# Microcontroller.net
KiCad netlist of a schematic drawn in Altium Designer
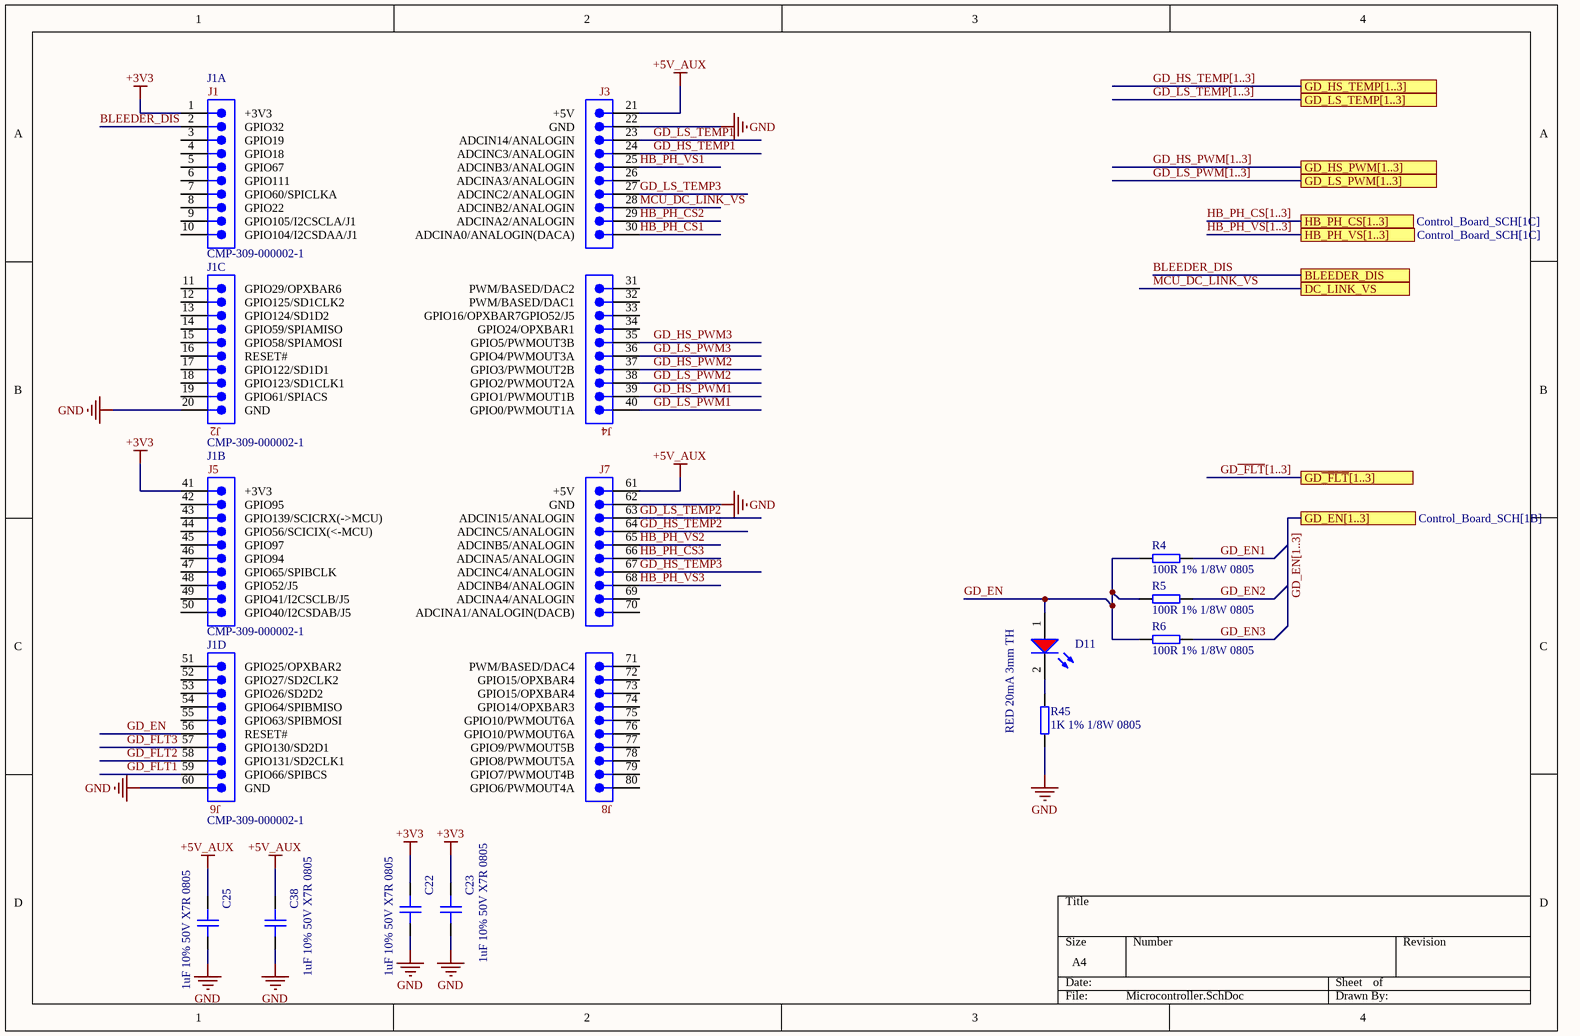
[diagram p0: Microcontroller.SchDoc]

(export (version "E")
  (design (tool "Eeschema 10.0.6"))
  (components
    (comp (ref "C22")
      (value "1uF 10% 50V X7R 0805")
      (footprint "CAPC2012X10N")
      (fields
        (field (name "MANUFACTURER PART NUMBER") "C2012X7R1H105K125AB")
        (field (name "MANUFACTURER") "TDK")
      )
      (libsource (lib "EMEA- E-Tech Racing- I'Escola d'Enginyeria de Barcelona Est") (part "68pF 10 630V C0G 0805"))
    )
    (comp (ref "C23")
      (value "1uF 10% 50V X7R 0805")
      (footprint "CAPC2012X10N")
      (fields
        (field (name "MANUFACTURER PART NUMBER") "C2012X7R1H105K125AB")
        (field (name "MANUFACTURER") "TDK")
      )
      (libsource (lib "EMEA- E-Tech Racing- I'Escola d'Enginyeria de Barcelona Est") (part "68pF 10 630V C0G 0805"))
    )
    (comp (ref "C25")
      (value "1uF 10% 50V X7R 0805")
      (footprint "CAPC2012X10N")
      (fields
        (field (name "MANUFACTURER PART NUMBER") "C2012X7R1H105K125AB")
        (field (name "MANUFACTURER") "TDK")
      )
      (libsource (lib "EMEA- E-Tech Racing- I'Escola d'Enginyeria de Barcelona Est") (part "68pF 10 630V C0G 0805"))
    )
    (comp (ref "C38")
      (value "1uF 10% 50V X7R 0805")
      (footprint "CAPC2012X10N")
      (fields
        (field (name "MANUFACTURER PART NUMBER") "C2012X7R1H105K125AB")
        (field (name "MANUFACTURER") "TDK")
      )
      (libsource (lib "EMEA- E-Tech Racing- I'Escola d'Enginyeria de Barcelona Est") (part "68pF 10 630V C0G 0805"))
    )
    (comp (ref "D11")
      (value "RED 20mA 3mm TH")
      (footprint "WL-TMRC_D3.95H5.3")
      (description "LED RED DIFFUSED 3MM ROUND T/H")
      (fields
        (field (name "MANUFACTURER") "Wurth Elektronik")
        (field (name "MANUFACTURER PART NUMBER") "151031SS06000")
      )
      (libsource (lib "EMEA- E-Tech Racing- I'Escola d'Enginyeria de Barcelona Est") (part "LED_Red_1A-2K"))
    )
    (comp (ref "J1")
      (value "CMP-309-000002-1")
      (footprint "LAUNCHXL-F28379D")
      (description "F28379D LaunchPad™ development kit for C2000™ Delfino™ MCU")
      (fields
        (field (name "MANUFACTURER") "Texas Instruments")
        (field (name "MANUFACTURER PART NUMBER") "LAUNCHXL-F28379D")
      )
      (libsource (lib "EMEA- E-Tech Racing- I'Escola d'Enginyeria de Barcelona Est") (part "CON80{colon} LAUNCHXL-F28379D"))
    )
    (comp (ref "R4")
      (value "100R 1% 1/8W 0805")
      (footprint "RESC2012X05N")
      (description "Res Thick Film 0805 100 Ohm 1% 0.125W ±100ppm/°C Molded SMD Paper T/R")
      (fields (field (name "TOLERANCE") "1%") (field (name "MANUFACTURER PART NUMBER") "RMCF0805FT100R"))
      (libsource (lib "EMEA- E-Tech Racing- I'Escola d'Enginyeria de Barcelona Est") (part "100R 1 1/8W 0805"))
    )
    (comp (ref "R5")
      (value "100R 1% 1/8W 0805")
      (footprint "RESC2012X05N")
      (description "Res Thick Film 0805 100 Ohm 1% 0.125W ±100ppm/°C Molded SMD Paper T/R")
      (fields (field (name "TOLERANCE") "1%") (field (name "MANUFACTURER PART NUMBER") "RMCF0805FT100R"))
      (libsource (lib "EMEA- E-Tech Racing- I'Escola d'Enginyeria de Barcelona Est") (part "100R 1 1/8W 0805"))
    )
    (comp (ref "R6")
      (value "100R 1% 1/8W 0805")
      (footprint "RESC2012X05N")
      (description "Res Thick Film 0805 100 Ohm 1% 0.125W ±100ppm/°C Molded SMD Paper T/R")
      (fields (field (name "TOLERANCE") "1%") (field (name "MANUFACTURER PART NUMBER") "RMCF0805FT100R"))
      (libsource (lib "EMEA- E-Tech Racing- I'Escola d'Enginyeria de Barcelona Est") (part "100R 1 1/8W 0805"))
    )
    (comp (ref "R45")
      (value "1K 1% 1/8W 0805")
      (footprint "RESC2012X05N")
      (description "Res Thick Film 0805 1K Ohm 1% 0.125W ±100ppm/°C Molded SMD Paper T/R")
      (fields (field (name "TOLERANCE") "1%") (field (name "MANUFACTURER") "Stackpole Electronics"))
      (libsource (lib "EMEA- E-Tech Racing- I'Escola d'Enginyeria de Barcelona Est") (part "100R 1 1/8W 0805"))
    )
  )
  (nets
    (net (code "1") (name "+3V3") (class "Default")
      (node (ref "C22") (pin "1") (pinfunction "1_1") (pintype "passive"))
      (node (ref "C23") (pin "1") (pinfunction "1_1") (pintype "passive"))
      (node (ref "J1") (pin "1") (pinfunction "+3V3_1") (pintype "passive"))
      (node (ref "J1") (pin "41") (pinfunction "+3V3_41") (pintype "passive"))
    )
    (net (code "2") (name "+5V_AUX") (class "Default")
      (node (ref "C25") (pin "1") (pinfunction "1_1") (pintype "passive"))
      (node (ref "C38") (pin "1") (pinfunction "1_1") (pintype "passive"))
      (node (ref "J1") (pin "21") (pinfunction "+5V_21") (pintype "passive"))
      (node (ref "J1") (pin "61") (pinfunction "+5V_61") (pintype "passive"))
    )
    (net (code "3") (name "/BLEEDER_DIS") (class "Default")
      (node (ref "J1") (pin "2") (pinfunction "GPIO32_2") (pintype "passive"))
    )
    (net (code "4") (name "/GD_EN") (class "Default")
      (node (ref "D11") (pin "1") (pinfunction "A_1") (pintype "passive"))
      (node (ref "J1") (pin "56") (pinfunction "RESET#_56") (pintype "passive"))
      (node (ref "R4") (pin "1") (pinfunction "1_1") (pintype "passive"))
      (node (ref "R5") (pin "1") (pinfunction "1_1") (pintype "passive"))
      (node (ref "R6") (pin "1") (pinfunction "1_1") (pintype "passive"))
    )
    (net (code "5") (name "/GD_EN1") (class "Default")
      (node (ref "R4") (pin "2") (pinfunction "2_2") (pintype "passive"))
    )
    (net (code "6") (name "/GD_EN2") (class "Default")
      (node (ref "R5") (pin "2") (pinfunction "2_2") (pintype "passive"))
    )
    (net (code "7") (name "/GD_EN3") (class "Default")
      (node (ref "R6") (pin "2") (pinfunction "2_2") (pintype "passive"))
    )
    (net (code "9") (name "/GD_HS_PWM1") (class "Default")
      (node (ref "J1") (pin "39") (pinfunction "GPIO1/PWMOUT1B_39") (pintype "passive"))
    )
    (net (code "10") (name "/GD_HS_PWM2") (class "Default")
      (node (ref "J1") (pin "37") (pinfunction "GPIO3/PWMOUT2B_37") (pintype "passive"))
    )
    (net (code "11") (name "/GD_HS_PWM3") (class "Default")
      (node (ref "J1") (pin "35") (pinfunction "GPIO5/PWMOUT3B_35") (pintype "passive"))
    )
    (net (code "13") (name "/GD_HS_TEMP1") (class "Default")
      (node (ref "J1") (pin "24") (pinfunction "ADCINC3/ANALOGIN_24") (pintype "passive"))
    )
    (net (code "14") (name "/GD_HS_TEMP2") (class "Default")
      (node (ref "J1") (pin "64") (pinfunction "ADCINC5/ANALOGIN_64") (pintype "passive"))
    )
    (net (code "15") (name "/GD_HS_TEMP3") (class "Default")
      (node (ref "J1") (pin "67") (pinfunction "ADCINC4/ANALOGIN_67") (pintype "passive"))
    )
    (net (code "17") (name "/GD_LS_PWM1") (class "Default")
      (node (ref "J1") (pin "40") (pinfunction "GPIO0/PWMOUT1A_40") (pintype "passive"))
    )
    (net (code "18") (name "/GD_LS_PWM2") (class "Default")
      (node (ref "J1") (pin "38") (pinfunction "GPIO2/PWMOUT2A_38") (pintype "passive"))
    )
    (net (code "19") (name "/GD_LS_PWM3") (class "Default")
      (node (ref "J1") (pin "36") (pinfunction "GPIO4/PWMOUT3A_36") (pintype "passive"))
    )
    (net (code "21") (name "/GD_LS_TEMP1") (class "Default")
      (node (ref "J1") (pin "23") (pinfunction "ADCIN14/ANALOGIN_23") (pintype "passive"))
    )
    (net (code "22") (name "/GD_LS_TEMP2") (class "Default")
      (node (ref "J1") (pin "63") (pinfunction "ADCIN15/ANALOGIN_63") (pintype "passive"))
    )
    (net (code "23") (name "/GD_LS_TEMP3") (class "Default")
      (node (ref "J1") (pin "27") (pinfunction "ADCINC2/ANALOGIN_27") (pintype "passive"))
    )
    (net (code "25") (name "/GD~{_FLT}1") (class "Default")
      (node (ref "J1") (pin "59") (pinfunction "GPIO66/SPIBCS_59") (pintype "passive"))
    )
    (net (code "26") (name "/GD~{_FLT}2") (class "Default")
      (node (ref "J1") (pin "58") (pinfunction "GPIO131/SD2CLK1_58") (pintype "passive"))
    )
    (net (code "27") (name "/GD~{_FLT}3") (class "Default")
      (node (ref "J1") (pin "57") (pinfunction "GPIO130/SD2D1_57") (pintype "passive"))
    )
    (net (code "29") (name "/HB_PH_CS1") (class "Default")
      (node (ref "J1") (pin "30") (pinfunction "ADCINA0/ANALOGIN(DACA)_30") (pintype "passive"))
    )
    (net (code "30") (name "/HB_PH_CS2") (class "Default")
      (node (ref "J1") (pin "29") (pinfunction "ADCINA2/ANALOGIN_29") (pintype "passive"))
    )
    (net (code "31") (name "/HB_PH_CS3") (class "Default")
      (node (ref "J1") (pin "66") (pinfunction "ADCINA5/ANALOGIN_66") (pintype "passive"))
    )
    (net (code "33") (name "/HB_PH_VS1") (class "Default")
      (node (ref "J1") (pin "25") (pinfunction "ADCINB3/ANALOGIN_25") (pintype "passive"))
    )
    (net (code "34") (name "/HB_PH_VS2") (class "Default")
      (node (ref "J1") (pin "65") (pinfunction "ADCINB5/ANALOGIN_65") (pintype "passive"))
    )
    (net (code "35") (name "/HB_PH_VS3") (class "Default")
      (node (ref "J1") (pin "68") (pinfunction "ADCINB4/ANALOGIN_68") (pintype "passive"))
    )
    (net (code "37") (name "/MCU_DC_LINK_VS") (class "Default")
      (node (ref "J1") (pin "28") (pinfunction "ADCINB2/ANALOGIN_28") (pintype "passive"))
    )
    (net (code "38") (name "GND") (class "Default")
      (node (ref "C22") (pin "2") (pinfunction "2_2") (pintype "passive"))
      (node (ref "C23") (pin "2") (pinfunction "2_2") (pintype "passive"))
      (node (ref "C25") (pin "2") (pinfunction "2_2") (pintype "passive"))
      (node (ref "C38") (pin "2") (pinfunction "2_2") (pintype "passive"))
      (node (ref "J1") (pin "20") (pinfunction "GND_20") (pintype "passive"))
      (node (ref "J1") (pin "22") (pinfunction "GND_22") (pintype "passive"))
      (node (ref "J1") (pin "60") (pinfunction "GND_60") (pintype "passive"))
      (node (ref "J1") (pin "62") (pinfunction "GND_62") (pintype "passive"))
      (node (ref "R45") (pin "1") (pinfunction "1_1") (pintype "passive"))
    )
    (net (code "39") (name "Net-(D11-K)") (class "Default")
      (node (ref "D11") (pin "2") (pinfunction "K_2") (pintype "passive"))
      (node (ref "R45") (pin "2") (pinfunction "2_2") (pintype "passive"))
    )
    (net (code "40") (name "unconnected-(J1A-ADCINA3{slash}ANALOGIN-Pad26)") (class "Default")
      (node (ref "J1") (pin "26") (pinfunction "ADCINA3/ANALOGIN_26") (pintype "passive"))
    )
    (net (code "41") (name "unconnected-(J1A-GPIO18-Pad4)") (class "Default")
      (node (ref "J1") (pin "4") (pinfunction "GPIO18_4") (pintype "passive"))
    )
    (net (code "42") (name "unconnected-(J1A-GPIO19-Pad3)") (class "Default")
      (node (ref "J1") (pin "3") (pinfunction "GPIO19_3") (pintype "passive"))
    )
    (net (code "43") (name "unconnected-(J1A-GPIO22-Pad8)") (class "Default")
      (node (ref "J1") (pin "8") (pinfunction "GPIO22_8") (pintype "passive"))
    )
    (net (code "44") (name "unconnected-(J1A-GPIO60{slash}SPICLKA-Pad7)") (class "Default")
      (node (ref "J1") (pin "7") (pinfunction "GPIO60/SPICLKA_7") (pintype "passive"))
    )
    (net (code "45") (name "unconnected-(J1A-GPIO67-Pad5)") (class "Default")
      (node (ref "J1") (pin "5") (pinfunction "GPIO67_5") (pintype "passive"))
    )
    (net (code "46") (name "unconnected-(J1A-GPIO104{slash}I2CSDAA{slash}J1-Pad10)") (class "Default")
      (node (ref "J1") (pin "10") (pinfunction "GPIO104/I2CSDAA/J1_10") (pintype "passive"))
    )
    (net (code "47") (name "unconnected-(J1A-GPIO105{slash}I2CSCLA{slash}J1-Pad9)") (class "Default")
      (node (ref "J1") (pin "9") (pinfunction "GPIO105/I2CSCLA/J1_9") (pintype "passive"))
    )
    (net (code "48") (name "unconnected-(J1A-GPIO111-Pad6)") (class "Default")
      (node (ref "J1") (pin "6") (pinfunction "GPIO111_6") (pintype "passive"))
    )
    (net (code "49") (name "unconnected-(J1B-ADCINA1{slash}ANALOGIN(DACB)-Pad70)") (class "Default")
      (node (ref "J1") (pin "70") (pinfunction "ADCINA1/ANALOGIN(DACB)_70") (pintype "passive"))
    )
    (net (code "50") (name "unconnected-(J1B-ADCINA4{slash}ANALOGIN-Pad69)") (class "Default")
      (node (ref "J1") (pin "69") (pinfunction "ADCINA4/ANALOGIN_69") (pintype "passive"))
    )
    (net (code "51") (name "unconnected-(J1B-GPIO40{slash}I2CSDAB{slash}J5-Pad50)") (class "Default")
      (node (ref "J1") (pin "50") (pinfunction "GPIO40/I2CSDAB/J5_50") (pintype "passive"))
    )
    (net (code "52") (name "unconnected-(J1B-GPIO41{slash}I2CSCLB{slash}J5-Pad49)") (class "Default")
      (node (ref "J1") (pin "49") (pinfunction "GPIO41/I2CSCLB/J5_49") (pintype "passive"))
    )
    (net (code "53") (name "unconnected-(J1B-GPIO52{slash}J5-Pad48)") (class "Default")
      (node (ref "J1") (pin "48") (pinfunction "GPIO52/J5_48") (pintype "passive"))
    )
    (net (code "54") (name "unconnected-(J1B-GPIO56{slash}SCICIX(<-MCU)-Pad44)") (class "Default")
      (node (ref "J1") (pin "44") (pinfunction "GPIO56/SCICIX(<-MCU)_44") (pintype "passive"))
    )
    (net (code "55") (name "unconnected-(J1B-GPIO65{slash}SPIBCLK-Pad47)") (class "Default")
      (node (ref "J1") (pin "47") (pinfunction "GPIO65/SPIBCLK_47") (pintype "passive"))
    )
    (net (code "56") (name "unconnected-(J1B-GPIO94-Pad46)") (class "Default")
      (node (ref "J1") (pin "46") (pinfunction "GPIO94_46") (pintype "passive"))
    )
    (net (code "57") (name "unconnected-(J1B-GPIO95-Pad42)") (class "Default")
      (node (ref "J1") (pin "42") (pinfunction "GPIO95_42") (pintype "passive"))
    )
    (net (code "58") (name "unconnected-(J1B-GPIO97-Pad45)") (class "Default")
      (node (ref "J1") (pin "45") (pinfunction "GPIO97_45") (pintype "passive"))
    )
    (net (code "59") (name "unconnected-(J1B-GPIO139{slash}SCICRX(->MCU)-Pad43)") (class "Default")
      (node (ref "J1") (pin "43") (pinfunction "GPIO139/SCICRX(->MCU)_43") (pintype "passive"))
    )
    (net (code "60") (name "unconnected-(J1C-GPIO16{slash}OPXBAR7GPIO52{slash}J5-Pad33)") (class "Default")
      (node (ref "J1") (pin "33") (pinfunction "GPIO16/OPXBAR7GPIO52/J5_33") (pintype "passive"))
    )
    (net (code "61") (name "unconnected-(J1C-GPIO24{slash}OPXBAR1-Pad34)") (class "Default")
      (node (ref "J1") (pin "34") (pinfunction "GPIO24/OPXBAR1_34") (pintype "passive"))
    )
    (net (code "62") (name "unconnected-(J1C-GPIO29{slash}OPXBAR6-Pad11)") (class "Default")
      (node (ref "J1") (pin "11") (pinfunction "GPIO29/OPXBAR6_11") (pintype "passive"))
    )
    (net (code "63") (name "unconnected-(J1C-GPIO58{slash}SPIAMOSI-Pad15)") (class "Default")
      (node (ref "J1") (pin "15") (pinfunction "GPIO58/SPIAMOSI_15") (pintype "passive"))
    )
    (net (code "64") (name "unconnected-(J1C-GPIO59{slash}SPIAMISO-Pad14)") (class "Default")
      (node (ref "J1") (pin "14") (pinfunction "GPIO59/SPIAMISO_14") (pintype "passive"))
    )
    (net (code "65") (name "unconnected-(J1C-GPIO61{slash}SPIACS-Pad19)") (class "Default")
      (node (ref "J1") (pin "19") (pinfunction "GPIO61/SPIACS_19") (pintype "passive"))
    )
    (net (code "66") (name "unconnected-(J1C-GPIO122{slash}SD1D1-Pad17)") (class "Default")
      (node (ref "J1") (pin "17") (pinfunction "GPIO122/SD1D1_17") (pintype "passive"))
    )
    (net (code "67") (name "unconnected-(J1C-GPIO123{slash}SD1CLK1-Pad18)") (class "Default")
      (node (ref "J1") (pin "18") (pinfunction "GPIO123/SD1CLK1_18") (pintype "passive"))
    )
    (net (code "68") (name "unconnected-(J1C-GPIO124{slash}SD1D2-Pad13)") (class "Default")
      (node (ref "J1") (pin "13") (pinfunction "GPIO124/SD1D2_13") (pintype "passive"))
    )
    (net (code "69") (name "unconnected-(J1C-GPIO125{slash}SD1CLK2-Pad12)") (class "Default")
      (node (ref "J1") (pin "12") (pinfunction "GPIO125/SD1CLK2_12") (pintype "passive"))
    )
    (net (code "70") (name "unconnected-(J1C-PWM{slash}BASED{slash}DAC1-Pad32)") (class "Default")
      (node (ref "J1") (pin "32") (pinfunction "PWM/BASED/DAC1_32") (pintype "passive"))
    )
    (net (code "71") (name "unconnected-(J1C-PWM{slash}BASED{slash}DAC2-Pad31)") (class "Default")
      (node (ref "J1") (pin "31") (pinfunction "PWM/BASED/DAC2_31") (pintype "passive"))
    )
    (net (code "72") (name "unconnected-(J1C-RESET#-Pad16)") (class "Default")
      (node (ref "J1") (pin "16") (pinfunction "RESET#_16") (pintype "passive"))
    )
    (net (code "73") (name "unconnected-(J1D-GPIO6{slash}PWMOUT4A-Pad80)") (class "Default")
      (node (ref "J1") (pin "80") (pinfunction "GPIO6/PWMOUT4A_80") (pintype "passive"))
    )
    (net (code "74") (name "unconnected-(J1D-GPIO7{slash}PWMOUT4B-Pad79)") (class "Default")
      (node (ref "J1") (pin "79") (pinfunction "GPIO7/PWMOUT4B_79") (pintype "passive"))
    )
    (net (code "75") (name "unconnected-(J1D-GPIO8{slash}PWMOUT5A-Pad78)") (class "Default")
      (node (ref "J1") (pin "78") (pinfunction "GPIO8/PWMOUT5A_78") (pintype "passive"))
    )
    (net (code "76") (name "unconnected-(J1D-GPIO9{slash}PWMOUT5B-Pad77)") (class "Default")
      (node (ref "J1") (pin "77") (pinfunction "GPIO9/PWMOUT5B_77") (pintype "passive"))
    )
    (net (code "77") (name "unconnected-(J1D-GPIO10{slash}PWMOUT6A-Pad75)") (class "Default")
      (node (ref "J1") (pin "75") (pinfunction "GPIO10/PWMOUT6A_75") (pintype "passive"))
    )
    (net (code "78") (name "unconnected-(J1D-GPIO10{slash}PWMOUT6A-Pad76)") (class "Default")
      (node (ref "J1") (pin "76") (pinfunction "GPIO10/PWMOUT6A_76") (pintype "passive"))
    )
    (net (code "79") (name "unconnected-(J1D-GPIO14{slash}OPXBAR3-Pad74)") (class "Default")
      (node (ref "J1") (pin "74") (pinfunction "GPIO14/OPXBAR3_74") (pintype "passive"))
    )
    (net (code "80") (name "unconnected-(J1D-GPIO15{slash}OPXBAR4-Pad72)") (class "Default")
      (node (ref "J1") (pin "72") (pinfunction "GPIO15/OPXBAR4_72") (pintype "passive"))
    )
    (net (code "81") (name "unconnected-(J1D-GPIO15{slash}OPXBAR4-Pad73)") (class "Default")
      (node (ref "J1") (pin "73") (pinfunction "GPIO15/OPXBAR4_73") (pintype "passive"))
    )
    (net (code "82") (name "unconnected-(J1D-GPIO25{slash}OPXBAR2-Pad51)") (class "Default")
      (node (ref "J1") (pin "51") (pinfunction "GPIO25/OPXBAR2_51") (pintype "passive"))
    )
    (net (code "83") (name "unconnected-(J1D-GPIO26{slash}SD2D2-Pad53)") (class "Default")
      (node (ref "J1") (pin "53") (pinfunction "GPIO26/SD2D2_53") (pintype "passive"))
    )
    (net (code "84") (name "unconnected-(J1D-GPIO27{slash}SD2CLK2-Pad52)") (class "Default")
      (node (ref "J1") (pin "52") (pinfunction "GPIO27/SD2CLK2_52") (pintype "passive"))
    )
    (net (code "85") (name "unconnected-(J1D-GPIO63{slash}SPIBMOSI-Pad55)") (class "Default")
      (node (ref "J1") (pin "55") (pinfunction "GPIO63/SPIBMOSI_55") (pintype "passive"))
    )
    (net (code "86") (name "unconnected-(J1D-GPIO64{slash}SPIBMISO-Pad54)") (class "Default")
      (node (ref "J1") (pin "54") (pinfunction "GPIO64/SPIBMISO_54") (pintype "passive"))
    )
    (net (code "87") (name "unconnected-(J1D-PWM{slash}BASED{slash}DAC4-Pad71)") (class "Default")
      (node (ref "J1") (pin "71") (pinfunction "PWM/BASED/DAC4_71") (pintype "passive"))
    )
  )
)
